# mLRS-rx-tx-E77-E22-dual-easysolder-v010.net
KiCad netlist of a schematic drawn in EAGLE
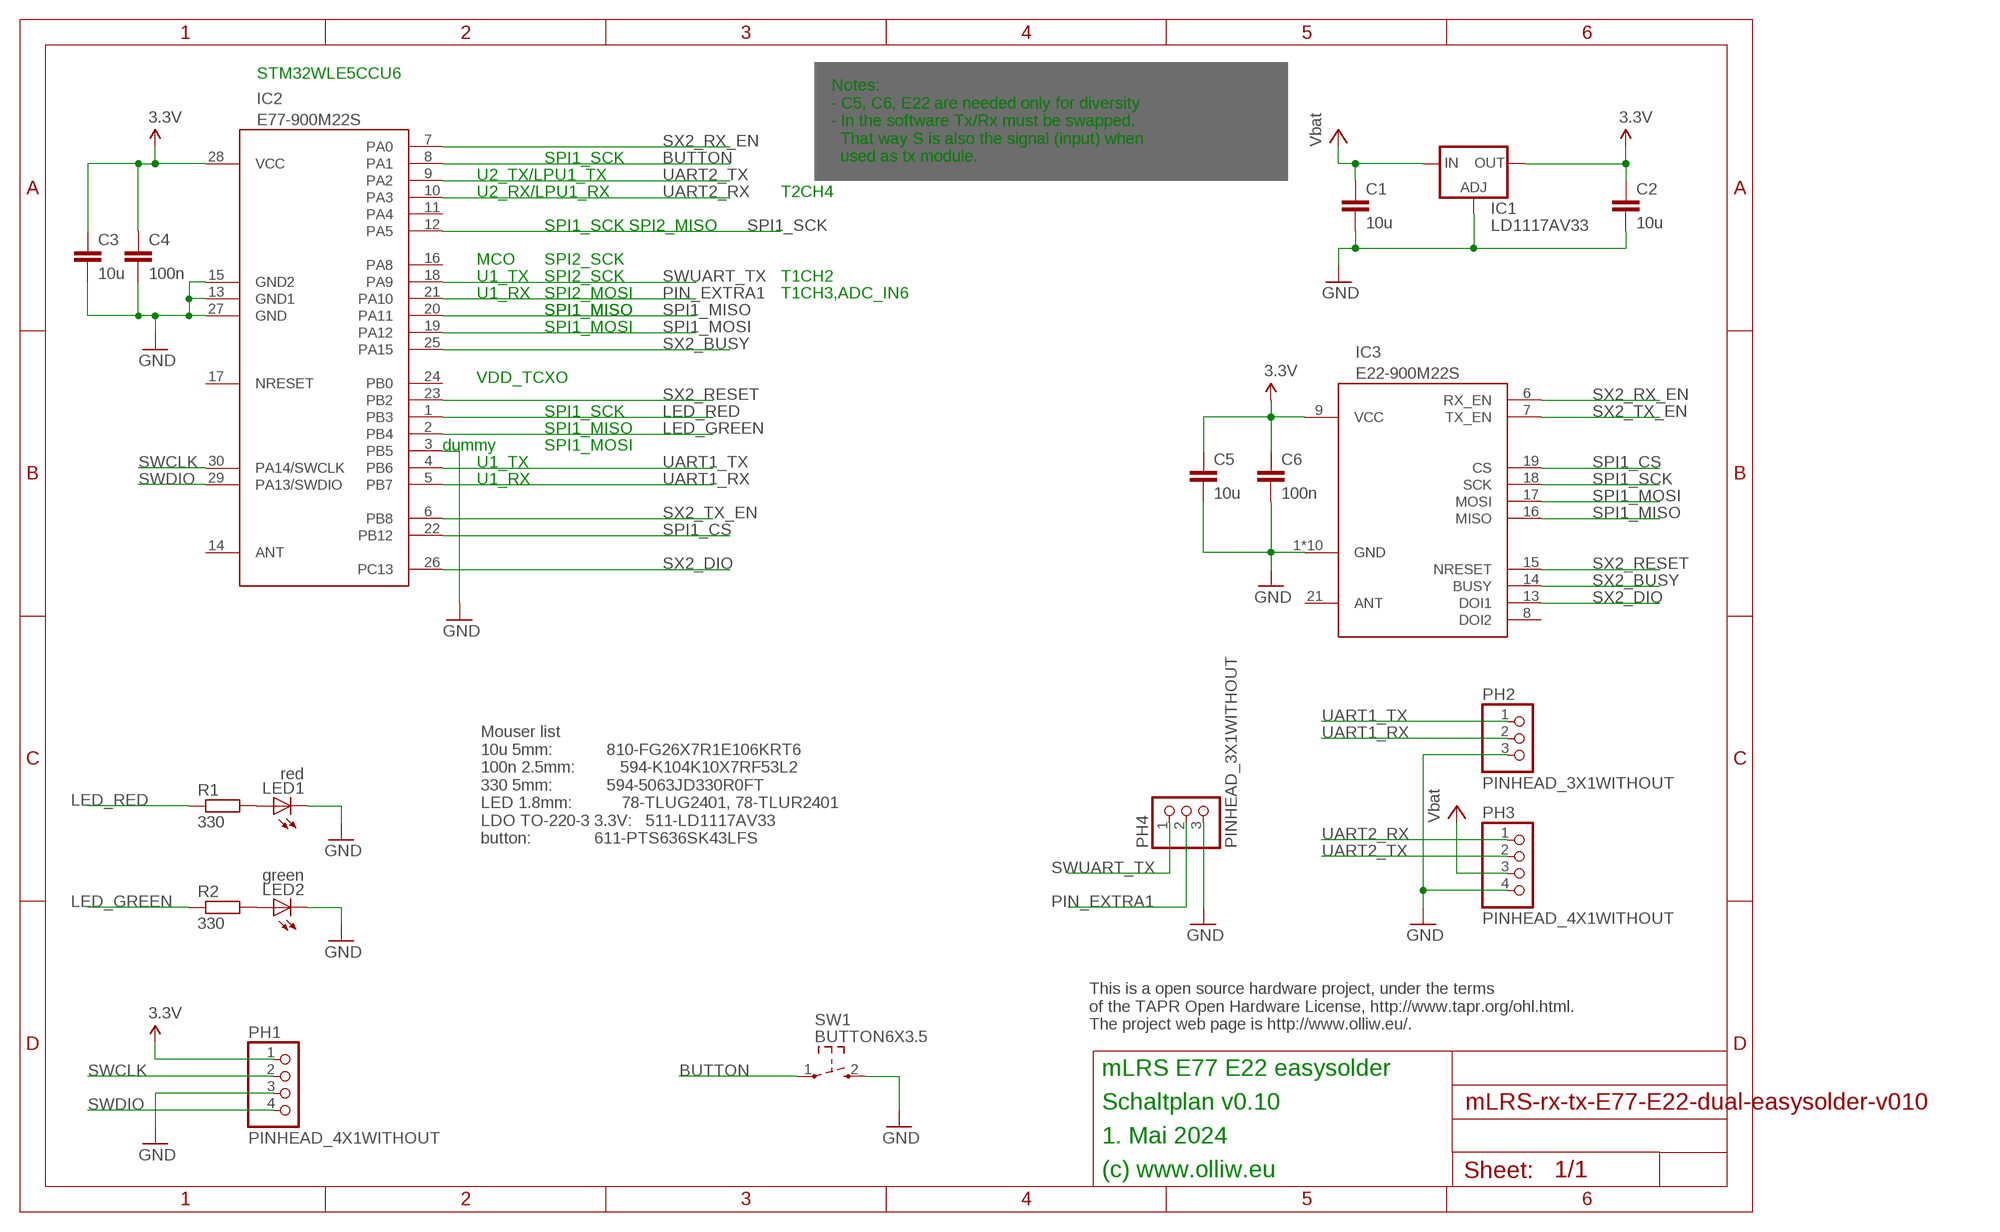
[diagram p0: schematic, sheet 1]

(export (version "E")
  (design (tool "Eeschema 10.0.6"))
  (components
    (comp (ref "C1")
      (value "10u")
      (footprint "eagle-import:C050-045X075")
      (libsource (lib "eagle-import") (part "C-EU050-045X075"))
    )
    (comp (ref "C2")
      (value "10u")
      (footprint "eagle-import:C050-045X075")
      (libsource (lib "eagle-import") (part "C-EU050-045X075"))
    )
    (comp (ref "C3")
      (value "10u")
      (footprint "eagle-import:C050-024X044")
      (libsource (lib "eagle-import") (part "C-EU050-024X044"))
    )
    (comp (ref "C4")
      (value "100n")
      (footprint "eagle-import:C025-024X044")
      (libsource (lib "eagle-import") (part "C-EU025-024X044"))
    )
    (comp (ref "C5")
      (value "10u")
      (footprint "eagle-import:C050-024X044")
      (libsource (lib "eagle-import") (part "C-EU050-024X044"))
    )
    (comp (ref "C6")
      (value "100n")
      (footprint "eagle-import:C025-024X044")
      (libsource (lib "eagle-import") (part "C-EU025-024X044"))
    )
    (comp (ref "IC1")
      (value "LD1117AV33")
      (footprint "eagle-import:TO220L1")
      (libsource (lib "eagle-import") (part "LD117A?V33"))
    )
    (comp (ref "IC2")
      (value "E77-900M22S")
      (footprint "eagle-import:E77-900M22S")
      (libsource (lib "eagle-import") (part "E77-900M22S"))
    )
    (comp (ref "IC3")
      (value "E22-900M22S")
      (footprint "eagle-import:E22-900M22S")
      (libsource (lib "eagle-import") (part "E22-900M22S"))
    )
    (comp (ref "LED1")
      (value "red")
      (footprint "eagle-import:LED1.8MM")
      (libsource (lib "eagle-import") (part "LED1.8MM"))
    )
    (comp (ref "LED2")
      (value "green")
      (footprint "eagle-import:LED1.8MM")
      (libsource (lib "eagle-import") (part "LED1.8MM"))
    )
    (comp (ref "PH1")
      (value "PINHEAD_4X1WITHOUT")
      (footprint "eagle-import:PINHEAD_4X1_WO")
      (libsource (lib "eagle-import") (part "PINHEAD_4X1WITHOUT"))
    )
    (comp (ref "PH2")
      (value "PINHEAD_3X1WITHOUT")
      (footprint "eagle-import:PINHEAD_3X1_WO")
      (libsource (lib "eagle-import") (part "PINHEAD_3X1WITHOUT"))
    )
    (comp (ref "PH3")
      (value "PINHEAD_4X1WITHOUT")
      (footprint "eagle-import:PINHEAD_4X1_WO")
      (libsource (lib "eagle-import") (part "PINHEAD_4X1WITHOUT"))
    )
    (comp (ref "PH4")
      (value "PINHEAD_3X1WITHOUT")
      (footprint "eagle-import:PINHEAD_3X1_WO")
      (libsource (lib "eagle-import") (part "PINHEAD_3X1WITHOUT"))
    )
    (comp (ref "R1")
      (value "330")
      (footprint "eagle-import:R0204_6.25")
      (libsource (lib "eagle-import") (part "R_EUR0204/6.25"))
    )
    (comp (ref "R2")
      (value "330")
      (footprint "eagle-import:R0204_6.25")
      (libsource (lib "eagle-import") (part "R_EUR0204/6.25"))
    )
    (comp (ref "SW1")
      (value "BUTTON6X3.5")
      (footprint "eagle-import:BUTTON-THT")
      (libsource (lib "eagle-import") (part "BUTTON6X3.5"))
    )
  )
  (nets
    (net (code "1") (name "/BUTTON") (class "Default")
      (node (ref "IC2") (pin "8") (pinfunction "PA1_8") (pintype "bidirectional"))
      (node (ref "SW1") (pin "1") (pinfunction "1_1") (pintype "passive"))
    )
    (net (code "2") (name "/LED_GREEN") (class "Default")
      (node (ref "IC2") (pin "2") (pinfunction "PB4_2") (pintype "bidirectional"))
      (node (ref "R2") (pin "1") (pinfunction "1_1") (pintype "passive"))
    )
    (net (code "3") (name "/LED_RED") (class "Default")
      (node (ref "IC2") (pin "1") (pinfunction "PB3_1") (pintype "bidirectional"))
      (node (ref "R1") (pin "1") (pinfunction "1_1") (pintype "passive"))
    )
    (net (code "4") (name "/PIN_EXTRA1") (class "Default")
      (node (ref "IC2") (pin "21") (pinfunction "PA10_21") (pintype "bidirectional"))
      (node (ref "PH4") (pin "2") (pinfunction "3_2") (pintype "passive"))
    )
    (net (code "5") (name "/SPI1_CS") (class "Default")
      (node (ref "IC2") (pin "22") (pinfunction "PB12_22") (pintype "bidirectional"))
      (node (ref "IC3") (pin "19") (pinfunction "CS_19") (pintype "bidirectional"))
    )
    (net (code "6") (name "/SPI1_MISO") (class "Default")
      (node (ref "IC2") (pin "20") (pinfunction "PA11_20") (pintype "bidirectional"))
      (node (ref "IC3") (pin "16") (pinfunction "MISO_16") (pintype "bidirectional"))
    )
    (net (code "7") (name "/SPI1_MOSI") (class "Default")
      (node (ref "IC2") (pin "19") (pinfunction "PA12_19") (pintype "bidirectional"))
      (node (ref "IC3") (pin "17") (pinfunction "MOSI_17") (pintype "bidirectional"))
    )
    (net (code "8") (name "/SPI1_SCK") (class "Default")
      (node (ref "IC2") (pin "12") (pinfunction "PA5_12") (pintype "bidirectional"))
      (node (ref "IC3") (pin "18") (pinfunction "SCK_18") (pintype "bidirectional"))
    )
    (net (code "9") (name "/SWCLK") (class "Default")
      (node (ref "IC2") (pin "30") (pinfunction "PA14/SWCLK_30") (pintype "bidirectional"))
      (node (ref "PH1") (pin "2") (pinfunction "2_2") (pintype "passive"))
    )
    (net (code "10") (name "/SWDIO") (class "Default")
      (node (ref "IC2") (pin "29") (pinfunction "PA13/SWDIO_29") (pintype "bidirectional"))
      (node (ref "PH1") (pin "4") (pinfunction "4_4") (pintype "passive"))
    )
    (net (code "11") (name "/SWUART_TX") (class "Default")
      (node (ref "IC2") (pin "18") (pinfunction "PA9_18") (pintype "bidirectional"))
      (node (ref "PH4") (pin "1") (pinfunction "1_1") (pintype "passive"))
    )
    (net (code "12") (name "/SX2_BUSY") (class "Default")
      (node (ref "IC2") (pin "25") (pinfunction "PA15_25") (pintype "bidirectional"))
      (node (ref "IC3") (pin "14") (pinfunction "BUSY_14") (pintype "bidirectional"))
    )
    (net (code "13") (name "/SX2_DIO") (class "Default")
      (node (ref "IC2") (pin "26") (pinfunction "PC13_26") (pintype "bidirectional"))
      (node (ref "IC3") (pin "13") (pinfunction "DOI1_13") (pintype "bidirectional"))
    )
    (net (code "14") (name "/SX2_RESET") (class "Default")
      (node (ref "IC2") (pin "23") (pinfunction "PB2_23") (pintype "bidirectional"))
      (node (ref "IC3") (pin "15") (pinfunction "NRESET_15") (pintype "input"))
    )
    (net (code "15") (name "/SX2_RX_EN") (class "Default")
      (node (ref "IC2") (pin "7") (pinfunction "PA0_7") (pintype "bidirectional"))
      (node (ref "IC3") (pin "6") (pinfunction "RX_EN_6") (pintype "bidirectional"))
    )
    (net (code "16") (name "/SX2_TX_EN") (class "Default")
      (node (ref "IC2") (pin "6") (pinfunction "PB8_6") (pintype "bidirectional"))
      (node (ref "IC3") (pin "7") (pinfunction "TX_EN_7") (pintype "bidirectional"))
    )
    (net (code "17") (name "/UART1_RX") (class "Default")
      (node (ref "IC2") (pin "5") (pinfunction "PB7_5") (pintype "bidirectional"))
      (node (ref "PH2") (pin "2") (pinfunction "3_2") (pintype "passive"))
    )
    (net (code "18") (name "/UART1_TX") (class "Default")
      (node (ref "IC2") (pin "4") (pinfunction "PB6_4") (pintype "bidirectional"))
      (node (ref "PH2") (pin "1") (pinfunction "1_1") (pintype "passive"))
    )
    (net (code "19") (name "/UART2_RX") (class "Default")
      (node (ref "IC2") (pin "10") (pinfunction "PA3_10") (pintype "bidirectional"))
      (node (ref "PH3") (pin "1") (pinfunction "1_1") (pintype "passive"))
    )
    (net (code "20") (name "/UART2_TX") (class "Default")
      (node (ref "IC2") (pin "9") (pinfunction "PA2_9") (pintype "bidirectional"))
      (node (ref "PH3") (pin "2") (pinfunction "2_2") (pintype "passive"))
    )
    (net (code "21") (name "3.3V") (class "Default")
      (node (ref "C2") (pin "1") (pinfunction "1_1") (pintype "passive"))
      (node (ref "C3") (pin "1") (pinfunction "1_1") (pintype "passive"))
      (node (ref "C4") (pin "1") (pinfunction "1_1") (pintype "passive"))
      (node (ref "C5") (pin "1") (pinfunction "1_1") (pintype "passive"))
      (node (ref "C6") (pin "1") (pinfunction "1_1") (pintype "passive"))
      (node (ref "IC1") (pin "2") (pinfunction "OUT_2") (pintype "passive"))
      (node (ref "IC2") (pin "28") (pinfunction "VCC_28") (pintype "power_in"))
      (node (ref "IC3") (pin "9") (pinfunction "VCC_9") (pintype "power_in"))
      (node (ref "PH1") (pin "1") (pinfunction "1_1") (pintype "passive"))
    )
    (net (code "22") (name "GND") (class "Default")
      (node (ref "C1") (pin "2") (pinfunction "2_2") (pintype "passive"))
      (node (ref "C2") (pin "2") (pinfunction "2_2") (pintype "passive"))
      (node (ref "C3") (pin "2") (pinfunction "2_2") (pintype "passive"))
      (node (ref "C4") (pin "2") (pinfunction "2_2") (pintype "passive"))
      (node (ref "C5") (pin "2") (pinfunction "2_2") (pintype "passive"))
      (node (ref "C6") (pin "2") (pinfunction "2_2") (pintype "passive"))
      (node (ref "IC1") (pin "1") (pinfunction "ADJ_1") (pintype "input"))
      (node (ref "IC2") (pin "13") (pinfunction "GND1_13") (pintype "power_in"))
      (node (ref "IC2") (pin "15") (pinfunction "GND2_15") (pintype "power_in"))
      (node (ref "IC2") (pin "27") (pinfunction "GND_27") (pintype "power_in"))
      (node (ref "IC2") (pin "3") (pinfunction "PB5_3") (pintype "bidirectional"))
      (node (ref "IC3") (pin "1") (pinfunction "GND_1") (pintype "power_in"))
      (node (ref "IC3") (pin "10") (pinfunction "GND_10") (pintype "power_in"))
      (node (ref "IC3") (pin "11") (pinfunction "GND_11") (pintype "power_in"))
      (node (ref "IC3") (pin "12") (pinfunction "GND_12") (pintype "power_in"))
      (node (ref "IC3") (pin "2") (pinfunction "GND_2") (pintype "power_in"))
      (node (ref "IC3") (pin "20") (pinfunction "GND_20") (pintype "power_in"))
      (node (ref "IC3") (pin "22") (pinfunction "GND_22") (pintype "power_in"))
      (node (ref "IC3") (pin "3") (pinfunction "GND_3") (pintype "power_in"))
      (node (ref "IC3") (pin "4") (pinfunction "GND_4") (pintype "power_in"))
      (node (ref "IC3") (pin "5") (pinfunction "GND_5") (pintype "power_in"))
      (node (ref "LED1") (pin "K") (pinfunction "C_K") (pintype "passive"))
      (node (ref "LED2") (pin "K") (pinfunction "C_K") (pintype "passive"))
      (node (ref "PH1") (pin "3") (pinfunction "3_3") (pintype "passive"))
      (node (ref "PH2") (pin "3") (pinfunction "5_3") (pintype "passive"))
      (node (ref "PH3") (pin "4") (pinfunction "4_4") (pintype "passive"))
      (node (ref "PH4") (pin "3") (pinfunction "5_3") (pintype "passive"))
      (node (ref "SW1") (pin "2") (pinfunction "3_2") (pintype "passive"))
    )
    (net (code "23") (name "Net-(LED1-PadA)") (class "Default")
      (node (ref "LED1") (pin "A") (pinfunction "A_A") (pintype "passive"))
      (node (ref "R1") (pin "2") (pinfunction "2_2") (pintype "passive"))
    )
    (net (code "24") (name "Net-(LED2-PadA)") (class "Default")
      (node (ref "LED2") (pin "A") (pinfunction "A_A") (pintype "passive"))
      (node (ref "R2") (pin "2") (pinfunction "2_2") (pintype "passive"))
    )
    (net (code "25") (name "Vbat") (class "Default")
      (node (ref "C1") (pin "1") (pinfunction "1_1") (pintype "passive"))
      (node (ref "IC1") (pin "3") (pinfunction "IN_3") (pintype "input"))
      (node (ref "PH3") (pin "3") (pinfunction "3_3") (pintype "passive"))
    )
    (net (code "26") (name "unconnected-(IC2-ANT-Pad14)") (class "Default")
      (node (ref "IC2") (pin "14") (pinfunction "ANT_14") (pintype "bidirectional"))
    )
    (net (code "27") (name "unconnected-(IC2-NRESET-Pad17)") (class "Default")
      (node (ref "IC2") (pin "17") (pinfunction "NRESET_17") (pintype "input"))
    )
    (net (code "28") (name "unconnected-(IC2-PA4-Pad11)") (class "Default")
      (node (ref "IC2") (pin "11") (pinfunction "PA4_11") (pintype "bidirectional"))
    )
    (net (code "29") (name "unconnected-(IC2-PA8-Pad16)") (class "Default")
      (node (ref "IC2") (pin "16") (pinfunction "PA8_16") (pintype "bidirectional"))
    )
    (net (code "30") (name "unconnected-(IC2-PB0-Pad24)") (class "Default")
      (node (ref "IC2") (pin "24") (pinfunction "PB0_24") (pintype "bidirectional"))
    )
    (net (code "31") (name "unconnected-(IC3-ANT-Pad21)") (class "Default")
      (node (ref "IC3") (pin "21") (pinfunction "ANT_21") (pintype "bidirectional"))
    )
    (net (code "32") (name "unconnected-(IC3-DOI2-Pad8)") (class "Default")
      (node (ref "IC3") (pin "8") (pinfunction "DOI2_8") (pintype "bidirectional"))
    )
  )
)
